# Schematic_RPi_GPBoard_V1.net
KiCad netlist of a schematic drawn in EAGLE
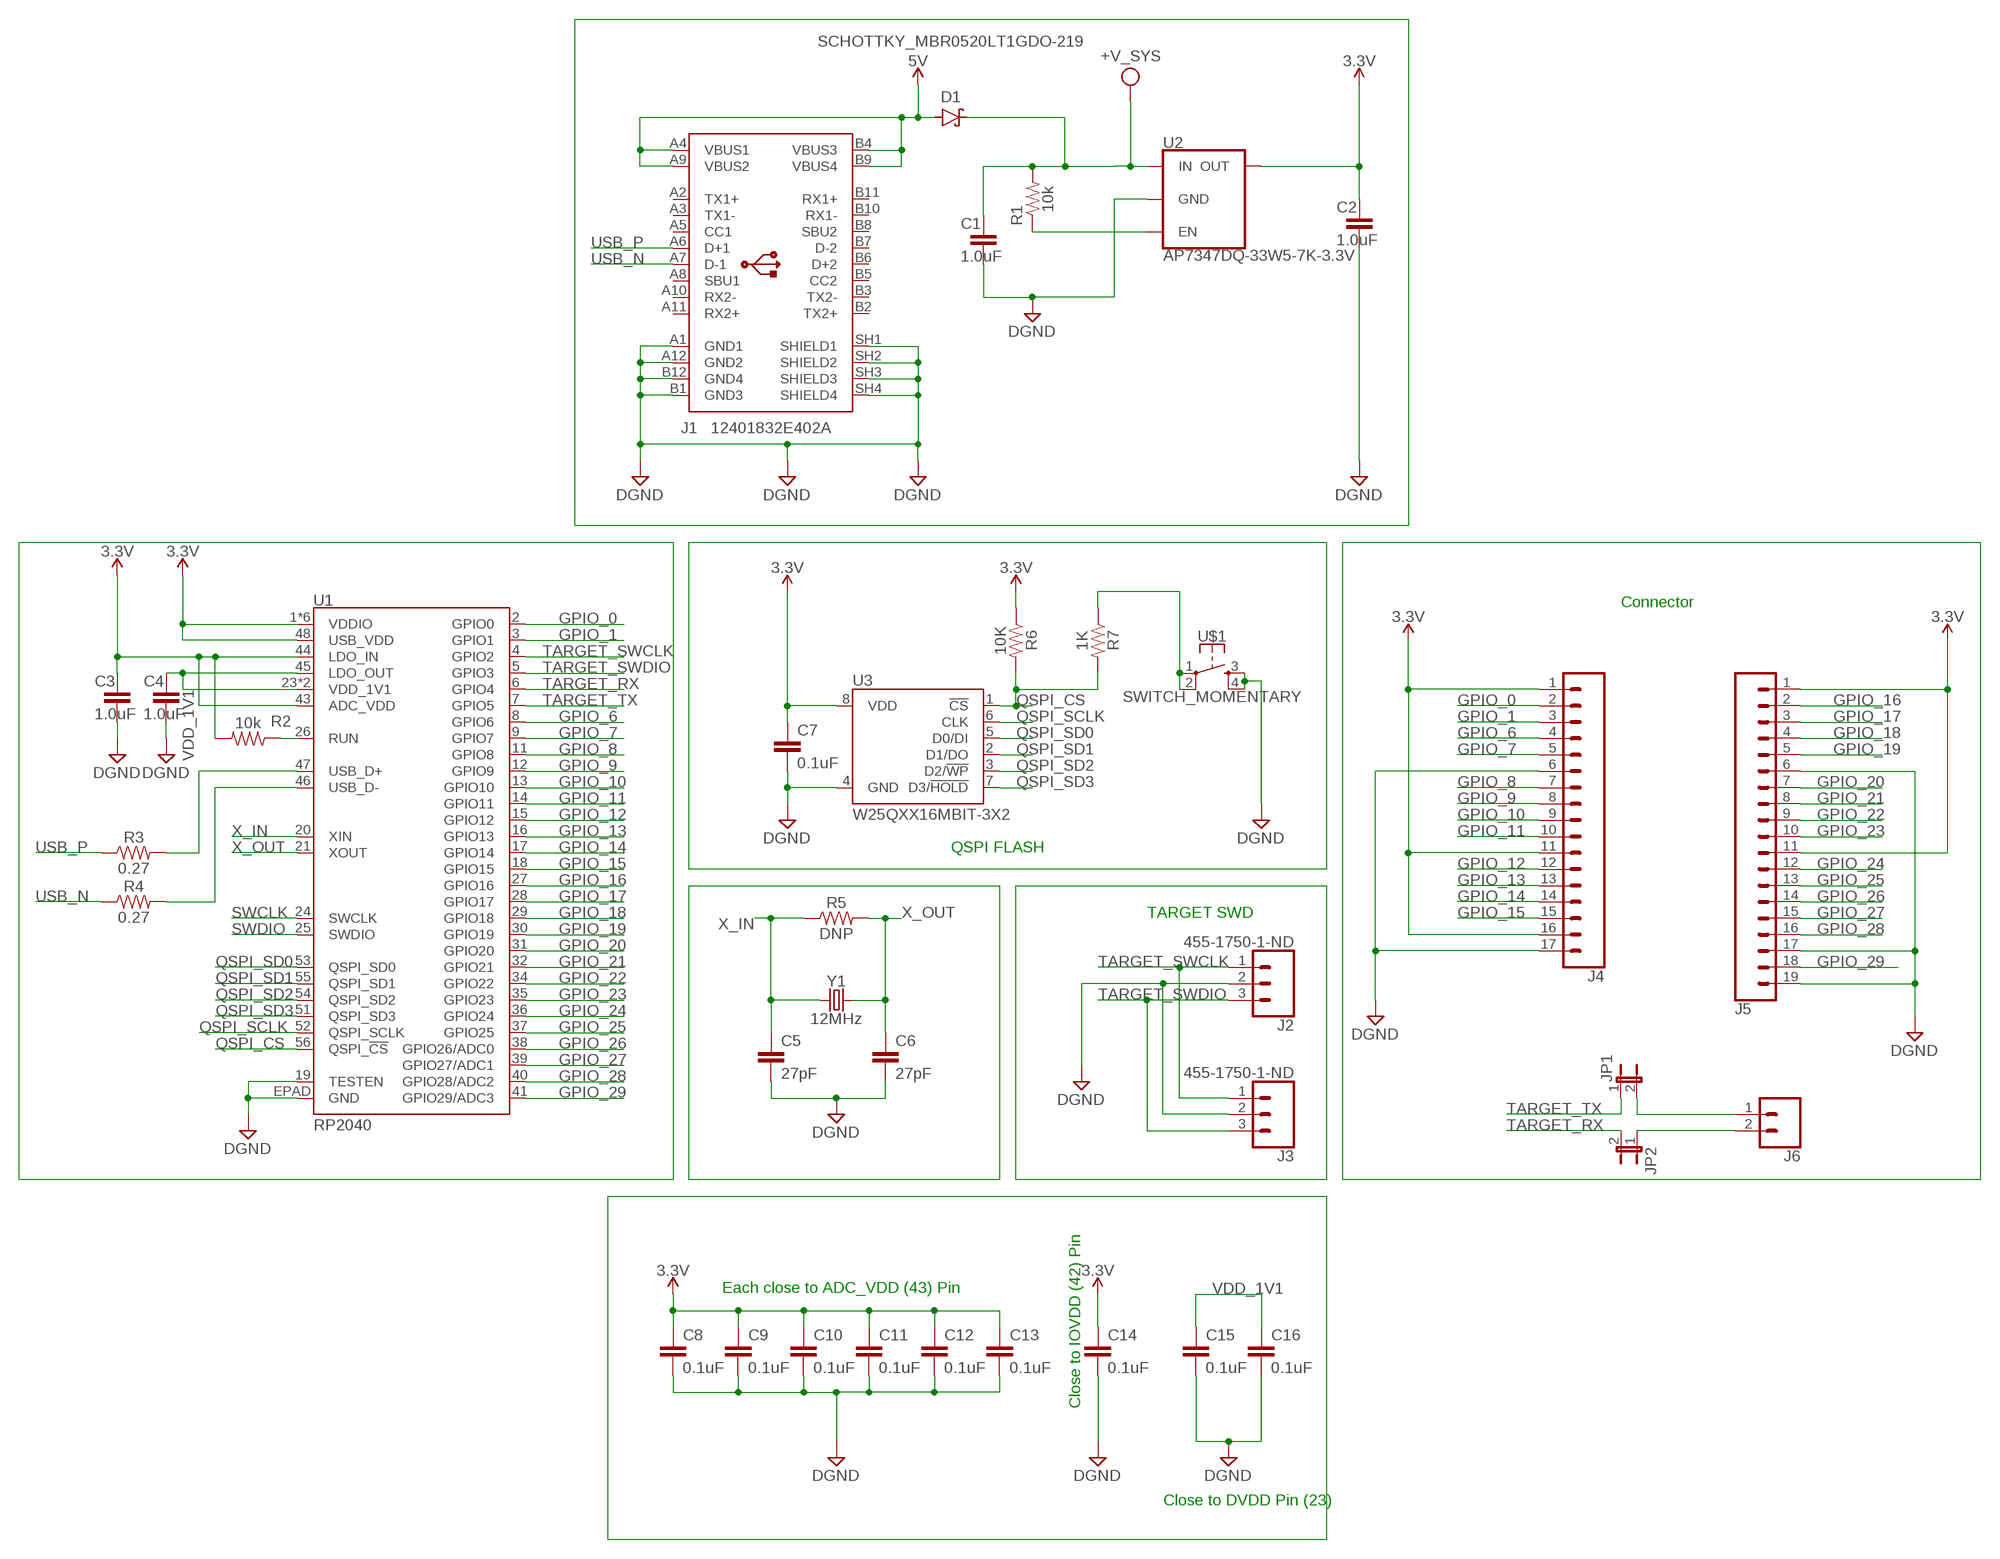
[diagram p0: schematic, sheet 1]

(export (version "E")
  (design (tool "Eeschema 10.0.6"))
  (components
    (comp (ref "C1")
      (value "1.0uF")
      (footprint "eagle-import:0603")
      (libsource (lib "eagle-import") (part "1.0UF-0603-16V-10%"))
    )
    (comp (ref "C2")
      (value "1.0uF")
      (footprint "eagle-import:0603")
      (libsource (lib "eagle-import") (part "1.0UF-0603-16V-10%"))
    )
    (comp (ref "C3")
      (value "1.0uF")
      (footprint "eagle-import:0603")
      (libsource (lib "eagle-import") (part "1.0UF-0603-16V-10%"))
    )
    (comp (ref "C4")
      (value "1.0uF")
      (footprint "eagle-import:0603")
      (libsource (lib "eagle-import") (part "1.0UF-0603-16V-10%"))
    )
    (comp (ref "C5")
      (value "27pF")
      (footprint "eagle-import:0603")
      (libsource (lib "eagle-import") (part "27PF-0603-50V-5%"))
    )
    (comp (ref "C6")
      (value "27pF")
      (footprint "eagle-import:0603")
      (libsource (lib "eagle-import") (part "27PF-0603-50V-5%"))
    )
    (comp (ref "C7")
      (value "0.1uF")
      (footprint "eagle-import:0603")
      (libsource (lib "eagle-import") (part "0.1UF-0603-25V-(+80/-20%)"))
    )
    (comp (ref "C8")
      (value "0.1uF")
      (footprint "eagle-import:0603")
      (libsource (lib "eagle-import") (part "0.1UF-0603-25V-(+80/-20%)"))
    )
    (comp (ref "C9")
      (value "0.1uF")
      (footprint "eagle-import:0603")
      (libsource (lib "eagle-import") (part "0.1UF-0603-25V-(+80/-20%)"))
    )
    (comp (ref "C10")
      (value "0.1uF")
      (footprint "eagle-import:0603")
      (libsource (lib "eagle-import") (part "0.1UF-0603-25V-(+80/-20%)"))
    )
    (comp (ref "C11")
      (value "0.1uF")
      (footprint "eagle-import:0603")
      (libsource (lib "eagle-import") (part "0.1UF-0603-25V-(+80/-20%)"))
    )
    (comp (ref "C12")
      (value "0.1uF")
      (footprint "eagle-import:0603")
      (libsource (lib "eagle-import") (part "0.1UF-0603-25V-(+80/-20%)"))
    )
    (comp (ref "C13")
      (value "0.1uF")
      (footprint "eagle-import:0603")
      (libsource (lib "eagle-import") (part "0.1UF-0603-25V-(+80/-20%)"))
    )
    (comp (ref "C14")
      (value "0.1uF")
      (footprint "eagle-import:0603")
      (libsource (lib "eagle-import") (part "0.1UF-0603-25V-(+80/-20%)"))
    )
    (comp (ref "C15")
      (value "0.1uF")
      (footprint "eagle-import:0603")
      (libsource (lib "eagle-import") (part "0.1UF-0603-25V-(+80/-20%)"))
    )
    (comp (ref "C16")
      (value "0.1uF")
      (footprint "eagle-import:0603")
      (libsource (lib "eagle-import") (part "0.1UF-0603-25V-(+80/-20%)"))
    )
    (comp (ref "D1")
      (value "SCHOTTKY_MBR0520LT1GDO-219")
      (footprint "eagle-import:SODFL3718X115")
      (fields (field (name "MANUFACTURER") "onsemi") (field (name "MPN") "MBR0520LT1G"))
      (libsource (lib "eagle-import") (part "SCHOTTKY_DO-219MBR0520LT1G"))
    )
    (comp (ref "J1")
      (value "12401832E402A")
      (footprint "eagle-import:12401832E402A")
      (fields (field (name "MANUFACTURER") "Amphenol ICC (Commercial Products)"))
      (libsource (lib "eagle-import") (part "12401832E402A"))
    )
    (comp (ref "J2")
      (value "455-1750-1-ND")
      (footprint "eagle-import:1X03")
      (libsource (lib "eagle-import") (part "CONN_03"))
    )
    (comp (ref "J3")
      (value "455-1750-1-ND")
      (footprint "eagle-import:1X03")
      (libsource (lib "eagle-import") (part "CONN_03"))
    )
    (comp (ref "J4")
      (value "CONN_17NOSILK")
      (footprint "eagle-import:1X17_NO_SILK")
      (libsource (lib "eagle-import") (part "CONN_17NOSILK"))
    )
    (comp (ref "J5")
      (value "CONN_19")
      (footprint "eagle-import:1X19")
      (libsource (lib "eagle-import") (part "CONN_19"))
    )
    (comp (ref "J6")
      (value "CONN_02")
      (footprint "eagle-import:1X02")
      (libsource (lib "eagle-import") (part "CONN_02"))
    )
    (comp (ref "JP1")
      (value "JUMPER-2SMD-NC")
      (footprint "eagle-import:SJ_2S")
      (libsource (lib "eagle-import") (part "JUMPER-2SMD-NC"))
    )
    (comp (ref "JP2")
      (value "JUMPER-2SMD-NC")
      (footprint "eagle-import:SJ_2S")
      (libsource (lib "eagle-import") (part "JUMPER-2SMD-NC"))
    )
    (comp (ref "R1")
      (value "10k")
      (footprint "eagle-import:AXIAL-0.3")
      (libsource (lib "eagle-import") (part "10KOHM-HORIZ-1/4W-1%"))
    )
    (comp (ref "R2")
      (value "10k")
      (footprint "eagle-import:AXIAL-0.3")
      (libsource (lib "eagle-import") (part "10KOHM-HORIZ-1/4W-1%"))
    )
    (comp (ref "R3")
      (value "0.27")
      (footprint "eagle-import:0603")
      (libsource (lib "eagle-import") (part "0.27OHM-0603-1/10W-1%"))
    )
    (comp (ref "R4")
      (value "0.27")
      (footprint "eagle-import:0603")
      (libsource (lib "eagle-import") (part "0.27OHM-0603-1/10W-1%"))
    )
    (comp (ref "R5")
      (value "DNP")
      (footprint "eagle-import:0603")
      (libsource (lib "eagle-import") (part "DNP-0603"))
    )
    (comp (ref "R6")
      (value "10K")
      (footprint "eagle-import:0603")
      (libsource (lib "eagle-import") (part "105OHM-0603-1/10W-1%"))
    )
    (comp (ref "R7")
      (value "1K")
      (footprint "eagle-import:0603")
      (libsource (lib "eagle-import") (part "105OHM-0603-1/10W-1%"))
    )
    (comp (ref "U$1")
      (value "SWITCH_MOMENTARY")
      (footprint "eagle-import:SWITCH-MOMENTARY-PTH-6.5MM")
      (libsource (lib "eagle-import") (part "SWITCH_MOMENTARY"))
    )
    (comp (ref "U1")
      (value "RP2040")
      (footprint "eagle-import:QFN-56")
      (libsource (lib "eagle-import") (part "RP2040"))
    )
    (comp (ref "U2")
      (value "AP7347DQ-33W5-7K-3.3V")
      (footprint "eagle-import:SOT25")
      (libsource (lib "eagle-import") (part "AP7347DQ-33W5-7K-3.3V"))
    )
    (comp (ref "U3")
      (value "W25QXX16MBIT-3X2")
      (footprint "eagle-import:USON-8")
      (libsource (lib "eagle-import") (part "W25QXX16MBIT-3X2"))
    )
    (comp (ref "Y1")
      (value "12MHz")
      (footprint "eagle-import:CRYSTAL-SMD-5X3.2-4PAD")
      (libsource (lib "eagle-import") (part "CRYSTAL-12MHZ{dblquote}"))
    )
  )
  (nets
    (net (code "1") (name "+V_SYS") (class "Default")
      (node (ref "C1") (pin "1") (pinfunction "1_1") (pintype "passive"))
      (node (ref "D1") (pin "1") (pinfunction "C_1") (pintype "passive"))
      (node (ref "R1") (pin "P$2") (pinfunction "2_P$2") (pintype "passive"))
      (node (ref "U2") (pin "1") (pinfunction "IN_1") (pintype "input"))
    )
    (net (code "2") (name "/GPIO_0") (class "Default")
      (node (ref "J4") (pin "2") (pinfunction "2_2") (pintype "passive"))
      (node (ref "U1") (pin "2") (pinfunction "GPIO0_2") (pintype "bidirectional"))
    )
    (net (code "3") (name "/GPIO_1") (class "Default")
      (node (ref "J4") (pin "3") (pinfunction "3_3") (pintype "passive"))
      (node (ref "U1") (pin "3") (pinfunction "GPIO1_3") (pintype "bidirectional"))
    )
    (net (code "4") (name "/GPIO_6") (class "Default")
      (node (ref "J4") (pin "4") (pinfunction "4_4") (pintype "passive"))
      (node (ref "U1") (pin "8") (pinfunction "GPIO6_8") (pintype "bidirectional"))
    )
    (net (code "5") (name "/GPIO_7") (class "Default")
      (node (ref "J4") (pin "5") (pinfunction "5_5") (pintype "passive"))
      (node (ref "U1") (pin "9") (pinfunction "GPIO7_9") (pintype "bidirectional"))
    )
    (net (code "6") (name "/GPIO_8") (class "Default")
      (node (ref "J4") (pin "7") (pinfunction "7_7") (pintype "passive"))
      (node (ref "U1") (pin "11") (pinfunction "GPIO8_11") (pintype "bidirectional"))
    )
    (net (code "7") (name "/GPIO_9") (class "Default")
      (node (ref "J4") (pin "8") (pinfunction "8_8") (pintype "passive"))
      (node (ref "U1") (pin "12") (pinfunction "GPIO9_12") (pintype "bidirectional"))
    )
    (net (code "8") (name "/GPIO_10") (class "Default")
      (node (ref "J4") (pin "9") (pinfunction "9_9") (pintype "passive"))
      (node (ref "U1") (pin "13") (pinfunction "GPIO10_13") (pintype "bidirectional"))
    )
    (net (code "9") (name "/GPIO_11") (class "Default")
      (node (ref "J4") (pin "10") (pinfunction "10_10") (pintype "passive"))
      (node (ref "U1") (pin "14") (pinfunction "GPIO11_14") (pintype "bidirectional"))
    )
    (net (code "10") (name "/GPIO_12") (class "Default")
      (node (ref "J4") (pin "12") (pinfunction "12_12") (pintype "passive"))
      (node (ref "U1") (pin "15") (pinfunction "GPIO12_15") (pintype "bidirectional"))
    )
    (net (code "11") (name "/GPIO_13") (class "Default")
      (node (ref "J4") (pin "13") (pinfunction "13_13") (pintype "passive"))
      (node (ref "U1") (pin "16") (pinfunction "GPIO13_16") (pintype "bidirectional"))
    )
    (net (code "12") (name "/GPIO_14") (class "Default")
      (node (ref "J4") (pin "14") (pinfunction "14_14") (pintype "passive"))
      (node (ref "U1") (pin "17") (pinfunction "GPIO14_17") (pintype "bidirectional"))
    )
    (net (code "13") (name "/GPIO_15") (class "Default")
      (node (ref "J4") (pin "15") (pinfunction "15_15") (pintype "passive"))
      (node (ref "U1") (pin "18") (pinfunction "GPIO15_18") (pintype "bidirectional"))
    )
    (net (code "14") (name "/GPIO_16") (class "Default")
      (node (ref "J5") (pin "2") (pinfunction "2_2") (pintype "passive"))
      (node (ref "U1") (pin "27") (pinfunction "GPIO16_27") (pintype "bidirectional"))
    )
    (net (code "15") (name "/GPIO_17") (class "Default")
      (node (ref "J5") (pin "3") (pinfunction "3_3") (pintype "passive"))
      (node (ref "U1") (pin "28") (pinfunction "GPIO17_28") (pintype "bidirectional"))
    )
    (net (code "16") (name "/GPIO_18") (class "Default")
      (node (ref "J5") (pin "4") (pinfunction "4_4") (pintype "passive"))
      (node (ref "U1") (pin "29") (pinfunction "GPIO18_29") (pintype "bidirectional"))
    )
    (net (code "17") (name "/GPIO_19") (class "Default")
      (node (ref "J5") (pin "5") (pinfunction "5_5") (pintype "passive"))
      (node (ref "U1") (pin "30") (pinfunction "GPIO19_30") (pintype "bidirectional"))
    )
    (net (code "18") (name "/GPIO_20") (class "Default")
      (node (ref "J5") (pin "7") (pinfunction "7_7") (pintype "passive"))
      (node (ref "U1") (pin "31") (pinfunction "GPIO20_31") (pintype "bidirectional"))
    )
    (net (code "19") (name "/GPIO_21") (class "Default")
      (node (ref "J5") (pin "8") (pinfunction "8_8") (pintype "passive"))
      (node (ref "U1") (pin "32") (pinfunction "GPIO21_32") (pintype "bidirectional"))
    )
    (net (code "20") (name "/GPIO_22") (class "Default")
      (node (ref "J5") (pin "9") (pinfunction "9_9") (pintype "passive"))
      (node (ref "U1") (pin "34") (pinfunction "GPIO22_34") (pintype "bidirectional"))
    )
    (net (code "21") (name "/GPIO_23") (class "Default")
      (node (ref "J5") (pin "10") (pinfunction "10_10") (pintype "passive"))
      (node (ref "U1") (pin "35") (pinfunction "GPIO23_35") (pintype "bidirectional"))
    )
    (net (code "22") (name "/GPIO_24") (class "Default")
      (node (ref "J5") (pin "12") (pinfunction "12_12") (pintype "passive"))
      (node (ref "U1") (pin "36") (pinfunction "GPIO24_36") (pintype "bidirectional"))
    )
    (net (code "23") (name "/GPIO_25") (class "Default")
      (node (ref "J5") (pin "13") (pinfunction "13_13") (pintype "passive"))
      (node (ref "U1") (pin "37") (pinfunction "GPIO25_37") (pintype "bidirectional"))
    )
    (net (code "24") (name "/GPIO_26") (class "Default")
      (node (ref "J5") (pin "14") (pinfunction "14_14") (pintype "passive"))
      (node (ref "U1") (pin "38") (pinfunction "GPIO26/ADC0_38") (pintype "bidirectional"))
    )
    (net (code "25") (name "/GPIO_27") (class "Default")
      (node (ref "J5") (pin "15") (pinfunction "15_15") (pintype "passive"))
      (node (ref "U1") (pin "39") (pinfunction "GPIO27/ADC1_39") (pintype "bidirectional"))
    )
    (net (code "26") (name "/GPIO_28") (class "Default")
      (node (ref "J5") (pin "16") (pinfunction "16_16") (pintype "passive"))
      (node (ref "U1") (pin "40") (pinfunction "GPIO28/ADC2_40") (pintype "bidirectional"))
    )
    (net (code "27") (name "/GPIO_29") (class "Default")
      (node (ref "J5") (pin "18") (pinfunction "18_18") (pintype "passive"))
      (node (ref "U1") (pin "41") (pinfunction "GPIO29/ADC3_41") (pintype "bidirectional"))
    )
    (net (code "28") (name "/QSPI_CS") (class "Default")
      (node (ref "R6") (pin "2") (pinfunction "2_2") (pintype "passive"))
      (node (ref "R7") (pin "2") (pinfunction "2_2") (pintype "passive"))
      (node (ref "U1") (pin "56") (pinfunction "QSPI_~{CS}_56") (pintype "bidirectional"))
      (node (ref "U3") (pin "1") (pinfunction "~{CS}_1") (pintype "bidirectional"))
    )
    (net (code "29") (name "/QSPI_SCLK") (class "Default")
      (node (ref "U1") (pin "52") (pinfunction "QSPI_SCLK_52") (pintype "bidirectional"))
      (node (ref "U3") (pin "6") (pinfunction "CLK_6") (pintype "bidirectional"))
    )
    (net (code "30") (name "/QSPI_SD0") (class "Default")
      (node (ref "U1") (pin "53") (pinfunction "QSPI_SD0_53") (pintype "bidirectional"))
      (node (ref "U3") (pin "5") (pinfunction "D0/DI_5") (pintype "bidirectional"))
    )
    (net (code "31") (name "/QSPI_SD1") (class "Default")
      (node (ref "U1") (pin "55") (pinfunction "QSPI_SD1_55") (pintype "bidirectional"))
      (node (ref "U3") (pin "2") (pinfunction "D1/DO_2") (pintype "bidirectional"))
    )
    (net (code "32") (name "/QSPI_SD2") (class "Default")
      (node (ref "U1") (pin "54") (pinfunction "QSPI_SD2_54") (pintype "bidirectional"))
      (node (ref "U3") (pin "3") (pinfunction "D2/~{WP}_3") (pintype "bidirectional"))
    )
    (net (code "33") (name "/QSPI_SD3") (class "Default")
      (node (ref "U1") (pin "51") (pinfunction "QSPI_SD3_51") (pintype "bidirectional"))
      (node (ref "U3") (pin "7") (pinfunction "D3/~{HOLD}_7") (pintype "bidirectional"))
    )
    (net (code "34") (name "/SWCLK") (class "Default")
      (node (ref "U1") (pin "24") (pinfunction "SWCLK_24") (pintype "bidirectional"))
    )
    (net (code "35") (name "/SWDIO") (class "Default")
      (node (ref "U1") (pin "25") (pinfunction "SWDIO_25") (pintype "bidirectional"))
    )
    (net (code "36") (name "/TARGET_RX") (class "Default")
      (node (ref "JP2") (pin "2") (pinfunction "2_2") (pintype "passive"))
      (node (ref "U1") (pin "6") (pinfunction "GPIO4_6") (pintype "bidirectional"))
    )
    (net (code "37") (name "/TARGET_SWCLK") (class "Default")
      (node (ref "J2") (pin "1") (pinfunction "1_1") (pintype "passive"))
      (node (ref "J3") (pin "1") (pinfunction "1_1") (pintype "passive"))
      (node (ref "U1") (pin "4") (pinfunction "GPIO2_4") (pintype "bidirectional"))
    )
    (net (code "38") (name "/TARGET_SWDIO") (class "Default")
      (node (ref "J2") (pin "3") (pinfunction "3_3") (pintype "passive"))
      (node (ref "J3") (pin "3") (pinfunction "3_3") (pintype "passive"))
      (node (ref "U1") (pin "5") (pinfunction "GPIO3_5") (pintype "bidirectional"))
    )
    (net (code "39") (name "/TARGET_TX") (class "Default")
      (node (ref "JP1") (pin "1") (pinfunction "1_1") (pintype "passive"))
      (node (ref "U1") (pin "7") (pinfunction "GPIO5_7") (pintype "bidirectional"))
    )
    (net (code "40") (name "/USB_N") (class "Default")
      (node (ref "J1") (pin "A7") (pinfunction "D-1_A7") (pintype "bidirectional"))
      (node (ref "R4") (pin "1") (pinfunction "1_1") (pintype "passive"))
    )
    (net (code "41") (name "/USB_P") (class "Default")
      (node (ref "J1") (pin "A6") (pinfunction "D+1_A6") (pintype "bidirectional"))
      (node (ref "R3") (pin "1") (pinfunction "1_1") (pintype "passive"))
    )
    (net (code "42") (name "/VDD_1V1") (class "Default")
      (node (ref "C15") (pin "1") (pinfunction "1_1") (pintype "passive"))
      (node (ref "C16") (pin "1") (pinfunction "1_1") (pintype "passive"))
      (node (ref "C4") (pin "1") (pinfunction "1_1") (pintype "passive"))
      (node (ref "U1") (pin "23") (pinfunction "VDD_1V1_23") (pintype "bidirectional"))
      (node (ref "U1") (pin "45") (pinfunction "LDO_OUT_45") (pintype "bidirectional"))
      (node (ref "U1") (pin "50") (pinfunction "VDD_1V1_50") (pintype "bidirectional"))
    )
    (net (code "43") (name "/X_IN") (class "Default")
      (node (ref "C5") (pin "1") (pinfunction "1_1") (pintype "passive"))
      (node (ref "R5") (pin "1") (pinfunction "1_1") (pintype "passive"))
      (node (ref "U1") (pin "20") (pinfunction "XIN_20") (pintype "bidirectional"))
      (node (ref "Y1") (pin "1") (pinfunction "1_1") (pintype "passive"))
    )
    (net (code "44") (name "/X_OUT") (class "Default")
      (node (ref "C6") (pin "1") (pinfunction "1_1") (pintype "passive"))
      (node (ref "R5") (pin "2") (pinfunction "2_2") (pintype "passive"))
      (node (ref "U1") (pin "21") (pinfunction "XOUT_21") (pintype "bidirectional"))
      (node (ref "Y1") (pin "3") (pinfunction "2_3") (pintype "passive"))
    )
    (net (code "45") (name "3.3V") (class "Default")
      (node (ref "C10") (pin "1") (pinfunction "1_1") (pintype "passive"))
      (node (ref "C11") (pin "1") (pinfunction "1_1") (pintype "passive"))
      (node (ref "C12") (pin "1") (pinfunction "1_1") (pintype "passive"))
      (node (ref "C13") (pin "1") (pinfunction "1_1") (pintype "passive"))
      (node (ref "C14") (pin "1") (pinfunction "1_1") (pintype "passive"))
      (node (ref "C2") (pin "1") (pinfunction "1_1") (pintype "passive"))
      (node (ref "C3") (pin "1") (pinfunction "1_1") (pintype "passive"))
      (node (ref "C7") (pin "1") (pinfunction "1_1") (pintype "passive"))
      (node (ref "C8") (pin "1") (pinfunction "1_1") (pintype "passive"))
      (node (ref "C9") (pin "1") (pinfunction "1_1") (pintype "passive"))
      (node (ref "J4") (pin "1") (pinfunction "1_1") (pintype "passive"))
      (node (ref "J4") (pin "11") (pinfunction "11_11") (pintype "passive"))
      (node (ref "J4") (pin "16") (pinfunction "16_16") (pintype "passive"))
      (node (ref "J5") (pin "1") (pinfunction "1_1") (pintype "passive"))
      (node (ref "J5") (pin "11") (pinfunction "11_11") (pintype "passive"))
      (node (ref "R2") (pin "P$2") (pinfunction "2_P$2") (pintype "passive"))
      (node (ref "R6") (pin "1") (pinfunction "1_1") (pintype "passive"))
      (node (ref "U1") (pin "1") (pinfunction "VDDIO_1") (pintype "bidirectional"))
      (node (ref "U1") (pin "10") (pinfunction "VDDIO_10") (pintype "bidirectional"))
      (node (ref "U1") (pin "22") (pinfunction "VDDIO_22") (pintype "bidirectional"))
      (node (ref "U1") (pin "33") (pinfunction "VDDIO_33") (pintype "bidirectional"))
      (node (ref "U1") (pin "42") (pinfunction "VDDIO_42") (pintype "bidirectional"))
      (node (ref "U1") (pin "43") (pinfunction "ADC_VDD_43") (pintype "bidirectional"))
      (node (ref "U1") (pin "44") (pinfunction "LDO_IN_44") (pintype "bidirectional"))
      (node (ref "U1") (pin "48") (pinfunction "USB_VDD_48") (pintype "bidirectional"))
      (node (ref "U1") (pin "49") (pinfunction "VDDIO_49") (pintype "bidirectional"))
      (node (ref "U2") (pin "5") (pinfunction "OUT_5") (pintype "passive"))
      (node (ref "U3") (pin "8") (pinfunction "VDD_8") (pintype "bidirectional"))
    )
    (net (code "46") (name "5V") (class "Default")
      (node (ref "D1") (pin "2") (pinfunction "A_2") (pintype "passive"))
      (node (ref "J1") (pin "A4") (pinfunction "VBUS1_A4") (pintype "power_in"))
      (node (ref "J1") (pin "A9") (pinfunction "VBUS2_A9") (pintype "power_in"))
      (node (ref "J1") (pin "B4") (pinfunction "VBUS3_B4") (pintype "power_in"))
      (node (ref "J1") (pin "B9") (pinfunction "VBUS4_B9") (pintype "power_in"))
    )
    (net (code "47") (name "DGND") (class "Default")
      (node (ref "C1") (pin "2") (pinfunction "2_2") (pintype "passive"))
      (node (ref "C10") (pin "2") (pinfunction "2_2") (pintype "passive"))
      (node (ref "C11") (pin "2") (pinfunction "2_2") (pintype "passive"))
      (node (ref "C12") (pin "2") (pinfunction "2_2") (pintype "passive"))
      (node (ref "C13") (pin "2") (pinfunction "2_2") (pintype "passive"))
      (node (ref "C14") (pin "2") (pinfunction "2_2") (pintype "passive"))
      (node (ref "C15") (pin "2") (pinfunction "2_2") (pintype "passive"))
      (node (ref "C16") (pin "2") (pinfunction "2_2") (pintype "passive"))
      (node (ref "C2") (pin "2") (pinfunction "2_2") (pintype "passive"))
      (node (ref "C3") (pin "2") (pinfunction "2_2") (pintype "passive"))
      (node (ref "C4") (pin "2") (pinfunction "2_2") (pintype "passive"))
      (node (ref "C5") (pin "2") (pinfunction "2_2") (pintype "passive"))
      (node (ref "C6") (pin "2") (pinfunction "2_2") (pintype "passive"))
      (node (ref "C7") (pin "2") (pinfunction "2_2") (pintype "passive"))
      (node (ref "C8") (pin "2") (pinfunction "2_2") (pintype "passive"))
      (node (ref "C9") (pin "2") (pinfunction "2_2") (pintype "passive"))
      (node (ref "J1") (pin "A1") (pinfunction "GND1_A1") (pintype "power_in"))
      (node (ref "J1") (pin "A12") (pinfunction "GND2_A12") (pintype "power_in"))
      (node (ref "J1") (pin "B1") (pinfunction "GND3_B1") (pintype "power_in"))
      (node (ref "J1") (pin "B12") (pinfunction "GND4_B12") (pintype "power_in"))
      (node (ref "J1") (pin "SH1") (pinfunction "SHIELD1_SH1") (pintype "power_in"))
      (node (ref "J1") (pin "SH2") (pinfunction "SHIELD2_SH2") (pintype "power_in"))
      (node (ref "J1") (pin "SH3") (pinfunction "SHIELD3_SH3") (pintype "power_in"))
      (node (ref "J1") (pin "SH4") (pinfunction "SHIELD4_SH4") (pintype "power_in"))
      (node (ref "J2") (pin "2") (pinfunction "2_2") (pintype "passive"))
      (node (ref "J3") (pin "2") (pinfunction "2_2") (pintype "passive"))
      (node (ref "J4") (pin "17") (pinfunction "17_17") (pintype "passive"))
      (node (ref "J4") (pin "6") (pinfunction "6_6") (pintype "passive"))
      (node (ref "J5") (pin "17") (pinfunction "17_17") (pintype "passive"))
      (node (ref "J5") (pin "19") (pinfunction "19_19") (pintype "passive"))
      (node (ref "J5") (pin "6") (pinfunction "6_6") (pintype "passive"))
      (node (ref "U$1") (pin "3") (pinfunction "3_3") (pintype "passive"))
      (node (ref "U$1") (pin "4") (pinfunction "4_4") (pintype "passive"))
      (node (ref "U1") (pin "19") (pinfunction "TESTEN_19") (pintype "bidirectional"))
      (node (ref "U1") (pin "EPAD") (pinfunction "GND_EPAD") (pintype "bidirectional"))
      (node (ref "U2") (pin "2") (pinfunction "GND_2") (pintype "input"))
      (node (ref "U3") (pin "4") (pinfunction "GND_4") (pintype "bidirectional"))
    )
    (net (code "48") (name "Net-(J6-Pad1)") (class "Default")
      (node (ref "J6") (pin "1") (pinfunction "1_1") (pintype "passive"))
      (node (ref "JP1") (pin "2") (pinfunction "2_2") (pintype "passive"))
    )
    (net (code "49") (name "Net-(J6-Pad2)") (class "Default")
      (node (ref "J6") (pin "2") (pinfunction "2_2") (pintype "passive"))
      (node (ref "JP2") (pin "1") (pinfunction "1_1") (pintype "passive"))
    )
    (net (code "50") (name "Net-(R1-1)") (class "Default")
      (node (ref "R1") (pin "P$1") (pinfunction "1_P$1") (pintype "passive"))
      (node (ref "U2") (pin "3") (pinfunction "EN_3") (pintype "input"))
    )
    (net (code "51") (name "Net-(R2-1)") (class "Default")
      (node (ref "R2") (pin "P$1") (pinfunction "1_P$1") (pintype "passive"))
      (node (ref "U1") (pin "26") (pinfunction "RUN_26") (pintype "bidirectional"))
    )
    (net (code "52") (name "Net-(R7-Pad1)") (class "Default")
      (node (ref "R7") (pin "1") (pinfunction "1_1") (pintype "passive"))
      (node (ref "U$1") (pin "1") (pinfunction "1_1") (pintype "passive"))
      (node (ref "U$1") (pin "2") (pinfunction "2_2") (pintype "passive"))
    )
    (net (code "53") (name "Net-(U1-USB_D+)") (class "Default")
      (node (ref "R3") (pin "2") (pinfunction "2_2") (pintype "passive"))
      (node (ref "U1") (pin "47") (pinfunction "USB_D+_47") (pintype "bidirectional"))
    )
    (net (code "54") (name "Net-(U1-USB_D-)") (class "Default")
      (node (ref "R4") (pin "2") (pinfunction "2_2") (pintype "passive"))
      (node (ref "U1") (pin "46") (pinfunction "USB_D-_46") (pintype "bidirectional"))
    )
    (net (code "55") (name "unconnected-(J1-CC1-PadA5)") (class "Default")
      (node (ref "J1") (pin "A5") (pinfunction "CC1_A5") (pintype "bidirectional"))
    )
    (net (code "56") (name "unconnected-(J1-CC2-PadB5)") (class "Default")
      (node (ref "J1") (pin "B5") (pinfunction "CC2_B5") (pintype "bidirectional"))
    )
    (net (code "57") (name "unconnected-(J1-D+2-PadB6)") (class "Default")
      (node (ref "J1") (pin "B6") (pinfunction "D+2_B6") (pintype "bidirectional"))
    )
    (net (code "58") (name "unconnected-(J1-D-2-PadB7)") (class "Default")
      (node (ref "J1") (pin "B7") (pinfunction "D-2_B7") (pintype "bidirectional"))
    )
    (net (code "59") (name "unconnected-(J1-RX1+-PadB11)") (class "Default")
      (node (ref "J1") (pin "B11") (pinfunction "RX1+_B11") (pintype "bidirectional"))
    )
    (net (code "60") (name "unconnected-(J1-RX1--PadB10)") (class "Default")
      (node (ref "J1") (pin "B10") (pinfunction "RX1-_B10") (pintype "bidirectional"))
    )
    (net (code "61") (name "unconnected-(J1-RX2+-PadA11)") (class "Default")
      (node (ref "J1") (pin "A11") (pinfunction "RX2+_A11") (pintype "bidirectional"))
    )
    (net (code "62") (name "unconnected-(J1-RX2--PadA10)") (class "Default")
      (node (ref "J1") (pin "A10") (pinfunction "RX2-_A10") (pintype "bidirectional"))
    )
    (net (code "63") (name "unconnected-(J1-SBU1-PadA8)") (class "Default")
      (node (ref "J1") (pin "A8") (pinfunction "SBU1_A8") (pintype "bidirectional"))
    )
    (net (code "64") (name "unconnected-(J1-SBU2-PadB8)") (class "Default")
      (node (ref "J1") (pin "B8") (pinfunction "SBU2_B8") (pintype "bidirectional"))
    )
    (net (code "65") (name "unconnected-(J1-TX1+-PadA2)") (class "Default")
      (node (ref "J1") (pin "A2") (pinfunction "TX1+_A2") (pintype "bidirectional"))
    )
    (net (code "66") (name "unconnected-(J1-TX1--PadA3)") (class "Default")
      (node (ref "J1") (pin "A3") (pinfunction "TX1-_A3") (pintype "bidirectional"))
    )
    (net (code "67") (name "unconnected-(J1-TX2+-PadB2)") (class "Default")
      (node (ref "J1") (pin "B2") (pinfunction "TX2+_B2") (pintype "bidirectional"))
    )
    (net (code "68") (name "unconnected-(J1-TX2--PadB3)") (class "Default")
      (node (ref "J1") (pin "B3") (pinfunction "TX2-_B3") (pintype "bidirectional"))
    )
  )
)
